# Ringlight.net
KiCad netlist of a schematic drawn in EAGLE
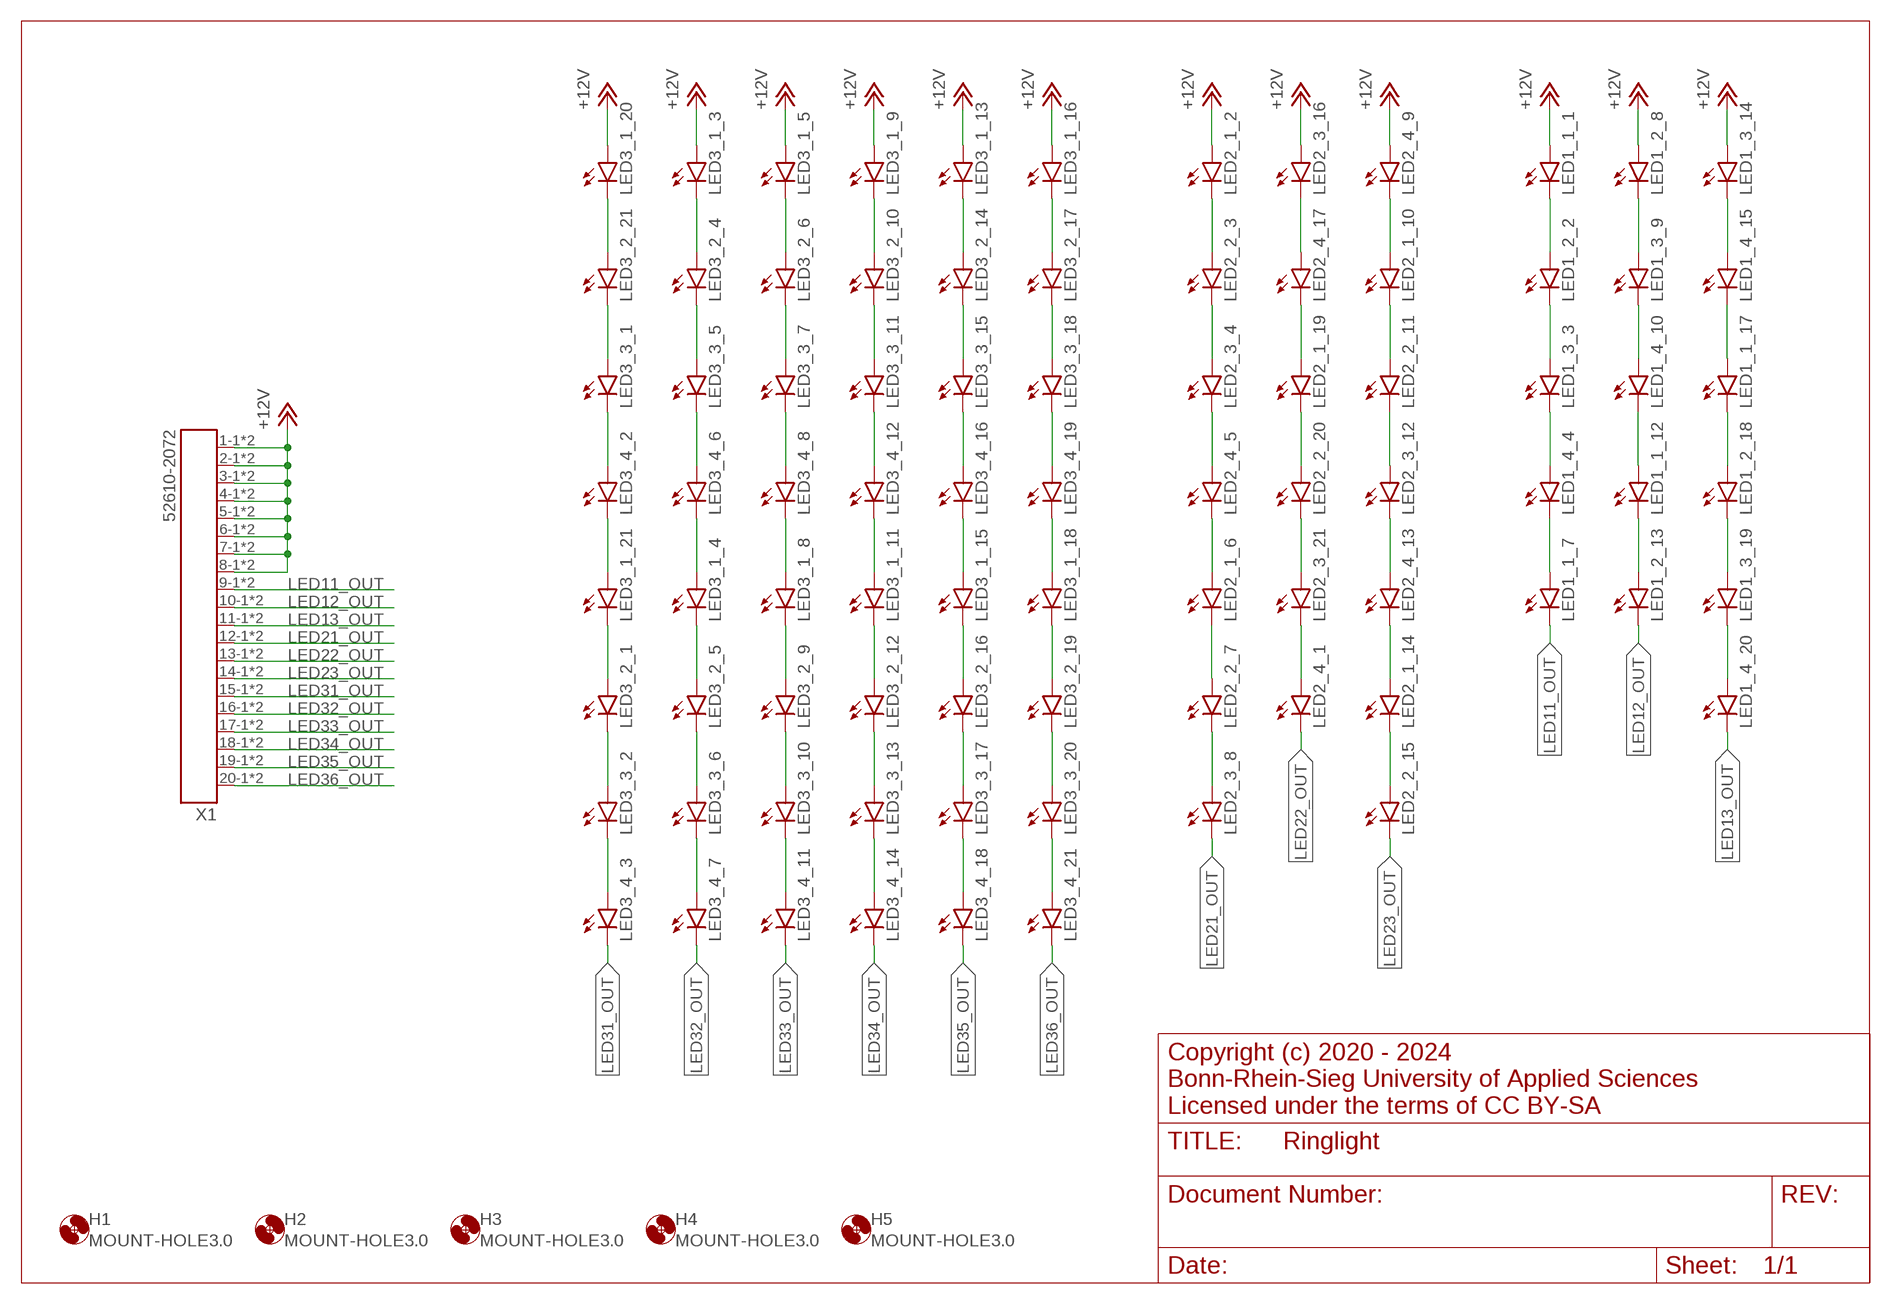
[diagram p0: schematic, sheet 1]

(export (version "E")
  (design (tool "Eeschema 10.0.6"))
  (components
    (comp (ref "H1")
      (value "MOUNT-HOLE3.0")
      (footprint "eagle-import:3,0")
      (libsource (lib "eagle-import") (part "MOUNT-HOLE3.0"))
    )
    (comp (ref "H2")
      (value "MOUNT-HOLE3.0")
      (footprint "eagle-import:3,0")
      (libsource (lib "eagle-import") (part "MOUNT-HOLE3.0"))
    )
    (comp (ref "H3")
      (value "MOUNT-HOLE3.0")
      (footprint "eagle-import:3,0")
      (libsource (lib "eagle-import") (part "MOUNT-HOLE3.0"))
    )
    (comp (ref "H4")
      (value "MOUNT-HOLE3.0")
      (footprint "eagle-import:3,0")
      (libsource (lib "eagle-import") (part "MOUNT-HOLE3.0"))
    )
    (comp (ref "H5")
      (value "MOUNT-HOLE3.0")
      (footprint "eagle-import:3,0")
      (libsource (lib "eagle-import") (part "MOUNT-HOLE3.0"))
    )
    (comp (ref "LED1_1_1")
      (value "LED5MM")
      (footprint "eagle-import:LED5MM")
      (libsource (lib "eagle-import") (part "LED5MM"))
    )
    (comp (ref "LED1_1_7")
      (value "LED5MM")
      (footprint "eagle-import:LED5MM")
      (libsource (lib "eagle-import") (part "LED5MM"))
    )
    (comp (ref "LED1_1_12")
      (value "LED5MM")
      (footprint "eagle-import:LED5MM")
      (libsource (lib "eagle-import") (part "LED5MM"))
    )
    (comp (ref "LED1_1_17")
      (value "LED5MM")
      (footprint "eagle-import:LED5MM")
      (libsource (lib "eagle-import") (part "LED5MM"))
    )
    (comp (ref "LED1_2_2")
      (value "LED5MM")
      (footprint "eagle-import:LED5MM")
      (libsource (lib "eagle-import") (part "LED5MM"))
    )
    (comp (ref "LED1_2_8")
      (value "LED5MM")
      (footprint "eagle-import:LED5MM")
      (libsource (lib "eagle-import") (part "LED5MM"))
    )
    (comp (ref "LED1_2_13")
      (value "LED5MM")
      (footprint "eagle-import:LED5MM")
      (libsource (lib "eagle-import") (part "LED5MM"))
    )
    (comp (ref "LED1_2_18")
      (value "LED5MM")
      (footprint "eagle-import:LED5MM")
      (libsource (lib "eagle-import") (part "LED5MM"))
    )
    (comp (ref "LED1_3_3")
      (value "LED5MM")
      (footprint "eagle-import:LED5MM")
      (libsource (lib "eagle-import") (part "LED5MM"))
    )
    (comp (ref "LED1_3_9")
      (value "LED5MM")
      (footprint "eagle-import:LED5MM")
      (libsource (lib "eagle-import") (part "LED5MM"))
    )
    (comp (ref "LED1_3_14")
      (value "LED5MM")
      (footprint "eagle-import:LED5MM")
      (libsource (lib "eagle-import") (part "LED5MM"))
    )
    (comp (ref "LED1_3_19")
      (value "LED5MM")
      (footprint "eagle-import:LED5MM")
      (libsource (lib "eagle-import") (part "LED5MM"))
    )
    (comp (ref "LED1_4_4")
      (value "LED5MM")
      (footprint "eagle-import:LED5MM")
      (libsource (lib "eagle-import") (part "LED5MM"))
    )
    (comp (ref "LED1_4_10")
      (value "LED5MM")
      (footprint "eagle-import:LED5MM")
      (libsource (lib "eagle-import") (part "LED5MM"))
    )
    (comp (ref "LED1_4_15")
      (value "LED5MM")
      (footprint "eagle-import:LED5MM")
      (libsource (lib "eagle-import") (part "LED5MM"))
    )
    (comp (ref "LED1_4_20")
      (value "LED5MM")
      (footprint "eagle-import:LED5MM")
      (libsource (lib "eagle-import") (part "LED5MM"))
    )
    (comp (ref "LED2_1_2")
      (value "LED5MM")
      (footprint "eagle-import:LED5MM")
      (libsource (lib "eagle-import") (part "LED5MM"))
    )
    (comp (ref "LED2_1_6")
      (value "LED5MM")
      (footprint "eagle-import:LED5MM")
      (libsource (lib "eagle-import") (part "LED5MM"))
    )
    (comp (ref "LED2_1_10")
      (value "LED5MM")
      (footprint "eagle-import:LED5MM")
      (libsource (lib "eagle-import") (part "LED5MM"))
    )
    (comp (ref "LED2_1_14")
      (value "LED5MM")
      (footprint "eagle-import:LED5MM")
      (libsource (lib "eagle-import") (part "LED5MM"))
    )
    (comp (ref "LED2_1_19")
      (value "LED5MM")
      (footprint "eagle-import:LED5MM")
      (libsource (lib "eagle-import") (part "LED5MM"))
    )
    (comp (ref "LED2_2_3")
      (value "LED5MM")
      (footprint "eagle-import:LED5MM")
      (libsource (lib "eagle-import") (part "LED5MM"))
    )
    (comp (ref "LED2_2_7")
      (value "LED5MM")
      (footprint "eagle-import:LED5MM")
      (libsource (lib "eagle-import") (part "LED5MM"))
    )
    (comp (ref "LED2_2_11")
      (value "LED5MM")
      (footprint "eagle-import:LED5MM")
      (libsource (lib "eagle-import") (part "LED5MM"))
    )
    (comp (ref "LED2_2_15")
      (value "LED5MM")
      (footprint "eagle-import:LED5MM")
      (libsource (lib "eagle-import") (part "LED5MM"))
    )
    (comp (ref "LED2_2_20")
      (value "LED5MM")
      (footprint "eagle-import:LED5MM")
      (libsource (lib "eagle-import") (part "LED5MM"))
    )
    (comp (ref "LED2_3_4")
      (value "LED5MM")
      (footprint "eagle-import:LED5MM")
      (libsource (lib "eagle-import") (part "LED5MM"))
    )
    (comp (ref "LED2_3_8")
      (value "LED5MM")
      (footprint "eagle-import:LED5MM")
      (libsource (lib "eagle-import") (part "LED5MM"))
    )
    (comp (ref "LED2_3_12")
      (value "LED5MM")
      (footprint "eagle-import:LED5MM")
      (libsource (lib "eagle-import") (part "LED5MM"))
    )
    (comp (ref "LED2_3_16")
      (value "LED5MM")
      (footprint "eagle-import:LED5MM")
      (libsource (lib "eagle-import") (part "LED5MM"))
    )
    (comp (ref "LED2_3_21")
      (value "LED5MM")
      (footprint "eagle-import:LED5MM")
      (libsource (lib "eagle-import") (part "LED5MM"))
    )
    (comp (ref "LED2_4_1")
      (value "LED5MM")
      (footprint "eagle-import:LED5MM")
      (libsource (lib "eagle-import") (part "LED5MM"))
    )
    (comp (ref "LED2_4_5")
      (value "LED5MM")
      (footprint "eagle-import:LED5MM")
      (libsource (lib "eagle-import") (part "LED5MM"))
    )
    (comp (ref "LED2_4_9")
      (value "LED5MM")
      (footprint "eagle-import:LED5MM")
      (libsource (lib "eagle-import") (part "LED5MM"))
    )
    (comp (ref "LED2_4_13")
      (value "LED5MM")
      (footprint "eagle-import:LED5MM")
      (libsource (lib "eagle-import") (part "LED5MM"))
    )
    (comp (ref "LED2_4_17")
      (value "LED5MM")
      (footprint "eagle-import:LED5MM")
      (libsource (lib "eagle-import") (part "LED5MM"))
    )
    (comp (ref "LED3_1_3")
      (value "LED5MM")
      (footprint "eagle-import:LED5MM")
      (libsource (lib "eagle-import") (part "LED5MM"))
    )
    (comp (ref "LED3_1_4")
      (value "LED5MM")
      (footprint "eagle-import:LED5MM")
      (libsource (lib "eagle-import") (part "LED5MM"))
    )
    (comp (ref "LED3_1_5")
      (value "LED5MM")
      (footprint "eagle-import:LED5MM")
      (libsource (lib "eagle-import") (part "LED5MM"))
    )
    (comp (ref "LED3_1_8")
      (value "LED5MM")
      (footprint "eagle-import:LED5MM")
      (libsource (lib "eagle-import") (part "LED5MM"))
    )
    (comp (ref "LED3_1_9")
      (value "LED5MM")
      (footprint "eagle-import:LED5MM")
      (libsource (lib "eagle-import") (part "LED5MM"))
    )
    (comp (ref "LED3_1_11")
      (value "LED5MM")
      (footprint "eagle-import:LED5MM")
      (libsource (lib "eagle-import") (part "LED5MM"))
    )
    (comp (ref "LED3_1_13")
      (value "LED5MM")
      (footprint "eagle-import:LED5MM")
      (libsource (lib "eagle-import") (part "LED5MM"))
    )
    (comp (ref "LED3_1_15")
      (value "LED5MM")
      (footprint "eagle-import:LED5MM")
      (libsource (lib "eagle-import") (part "LED5MM"))
    )
    (comp (ref "LED3_1_16")
      (value "LED5MM")
      (footprint "eagle-import:LED5MM")
      (libsource (lib "eagle-import") (part "LED5MM"))
    )
    (comp (ref "LED3_1_18")
      (value "LED5MM")
      (footprint "eagle-import:LED5MM")
      (libsource (lib "eagle-import") (part "LED5MM"))
    )
    (comp (ref "LED3_1_20")
      (value "LED5MM")
      (footprint "eagle-import:LED5MM")
      (libsource (lib "eagle-import") (part "LED5MM"))
    )
    (comp (ref "LED3_1_21")
      (value "LED5MM")
      (footprint "eagle-import:LED5MM")
      (libsource (lib "eagle-import") (part "LED5MM"))
    )
    (comp (ref "LED3_2_1")
      (value "LED5MM")
      (footprint "eagle-import:LED5MM")
      (libsource (lib "eagle-import") (part "LED5MM"))
    )
    (comp (ref "LED3_2_4")
      (value "LED5MM")
      (footprint "eagle-import:LED5MM")
      (libsource (lib "eagle-import") (part "LED5MM"))
    )
    (comp (ref "LED3_2_5")
      (value "LED5MM")
      (footprint "eagle-import:LED5MM")
      (libsource (lib "eagle-import") (part "LED5MM"))
    )
    (comp (ref "LED3_2_6")
      (value "LED5MM")
      (footprint "eagle-import:LED5MM")
      (libsource (lib "eagle-import") (part "LED5MM"))
    )
    (comp (ref "LED3_2_9")
      (value "LED5MM")
      (footprint "eagle-import:LED5MM")
      (libsource (lib "eagle-import") (part "LED5MM"))
    )
    (comp (ref "LED3_2_10")
      (value "LED5MM")
      (footprint "eagle-import:LED5MM")
      (libsource (lib "eagle-import") (part "LED5MM"))
    )
    (comp (ref "LED3_2_12")
      (value "LED5MM")
      (footprint "eagle-import:LED5MM")
      (libsource (lib "eagle-import") (part "LED5MM"))
    )
    (comp (ref "LED3_2_14")
      (value "LED5MM")
      (footprint "eagle-import:LED5MM")
      (libsource (lib "eagle-import") (part "LED5MM"))
    )
    (comp (ref "LED3_2_16")
      (value "LED5MM")
      (footprint "eagle-import:LED5MM")
      (libsource (lib "eagle-import") (part "LED5MM"))
    )
    (comp (ref "LED3_2_17")
      (value "LED5MM")
      (footprint "eagle-import:LED5MM")
      (libsource (lib "eagle-import") (part "LED5MM"))
    )
    (comp (ref "LED3_2_19")
      (value "LED5MM")
      (footprint "eagle-import:LED5MM")
      (libsource (lib "eagle-import") (part "LED5MM"))
    )
    (comp (ref "LED3_2_21")
      (value "LED5MM")
      (footprint "eagle-import:LED5MM")
      (libsource (lib "eagle-import") (part "LED5MM"))
    )
    (comp (ref "LED3_3_1")
      (value "LED5MM")
      (footprint "eagle-import:LED5MM")
      (libsource (lib "eagle-import") (part "LED5MM"))
    )
    (comp (ref "LED3_3_2")
      (value "LED5MM")
      (footprint "eagle-import:LED5MM")
      (libsource (lib "eagle-import") (part "LED5MM"))
    )
    (comp (ref "LED3_3_5")
      (value "LED5MM")
      (footprint "eagle-import:LED5MM")
      (libsource (lib "eagle-import") (part "LED5MM"))
    )
    (comp (ref "LED3_3_6")
      (value "LED5MM")
      (footprint "eagle-import:LED5MM")
      (libsource (lib "eagle-import") (part "LED5MM"))
    )
    (comp (ref "LED3_3_7")
      (value "LED5MM")
      (footprint "eagle-import:LED5MM")
      (libsource (lib "eagle-import") (part "LED5MM"))
    )
    (comp (ref "LED3_3_10")
      (value "LED5MM")
      (footprint "eagle-import:LED5MM")
      (libsource (lib "eagle-import") (part "LED5MM"))
    )
    (comp (ref "LED3_3_11")
      (value "LED5MM")
      (footprint "eagle-import:LED5MM")
      (libsource (lib "eagle-import") (part "LED5MM"))
    )
    (comp (ref "LED3_3_13")
      (value "LED5MM")
      (footprint "eagle-import:LED5MM")
      (libsource (lib "eagle-import") (part "LED5MM"))
    )
    (comp (ref "LED3_3_15")
      (value "LED5MM")
      (footprint "eagle-import:LED5MM")
      (libsource (lib "eagle-import") (part "LED5MM"))
    )
    (comp (ref "LED3_3_17")
      (value "LED5MM")
      (footprint "eagle-import:LED5MM")
      (libsource (lib "eagle-import") (part "LED5MM"))
    )
    (comp (ref "LED3_3_18")
      (value "LED5MM")
      (footprint "eagle-import:LED5MM")
      (libsource (lib "eagle-import") (part "LED5MM"))
    )
    (comp (ref "LED3_3_20")
      (value "LED5MM")
      (footprint "eagle-import:LED5MM")
      (libsource (lib "eagle-import") (part "LED5MM"))
    )
    (comp (ref "LED3_4_2")
      (value "LED5MM")
      (footprint "eagle-import:LED5MM")
      (libsource (lib "eagle-import") (part "LED5MM"))
    )
    (comp (ref "LED3_4_3")
      (value "LED5MM")
      (footprint "eagle-import:LED5MM")
      (libsource (lib "eagle-import") (part "LED5MM"))
    )
    (comp (ref "LED3_4_6")
      (value "LED5MM")
      (footprint "eagle-import:LED5MM")
      (libsource (lib "eagle-import") (part "LED5MM"))
    )
    (comp (ref "LED3_4_7")
      (value "LED5MM")
      (footprint "eagle-import:LED5MM")
      (libsource (lib "eagle-import") (part "LED5MM"))
    )
    (comp (ref "LED3_4_8")
      (value "LED5MM")
      (footprint "eagle-import:LED5MM")
      (libsource (lib "eagle-import") (part "LED5MM"))
    )
    (comp (ref "LED3_4_11")
      (value "LED5MM")
      (footprint "eagle-import:LED5MM")
      (libsource (lib "eagle-import") (part "LED5MM"))
    )
    (comp (ref "LED3_4_12")
      (value "LED5MM")
      (footprint "eagle-import:LED5MM")
      (libsource (lib "eagle-import") (part "LED5MM"))
    )
    (comp (ref "LED3_4_14")
      (value "LED5MM")
      (footprint "eagle-import:LED5MM")
      (libsource (lib "eagle-import") (part "LED5MM"))
    )
    (comp (ref "LED3_4_16")
      (value "LED5MM")
      (footprint "eagle-import:LED5MM")
      (libsource (lib "eagle-import") (part "LED5MM"))
    )
    (comp (ref "LED3_4_18")
      (value "LED5MM")
      (footprint "eagle-import:LED5MM")
      (libsource (lib "eagle-import") (part "LED5MM"))
    )
    (comp (ref "LED3_4_19")
      (value "LED5MM")
      (footprint "eagle-import:LED5MM")
      (libsource (lib "eagle-import") (part "LED5MM"))
    )
    (comp (ref "LED3_4_21")
      (value "LED5MM")
      (footprint "eagle-import:LED5MM")
      (libsource (lib "eagle-import") (part "LED5MM"))
    )
    (comp (ref "X1")
      (value "52610-2072")
      (footprint "eagle-import:52610-2072")
      (libsource (lib "eagle-import") (part "52610-2072"))
    )
  )
  (nets
    (net (code "1") (name "+12V") (class "Default")
      (node (ref "LED1_1_1") (pin "A") (pinfunction "A_A") (pintype "passive"))
      (node (ref "LED1_2_8") (pin "A") (pinfunction "A_A") (pintype "passive"))
      (node (ref "LED1_3_14") (pin "A") (pinfunction "A_A") (pintype "passive"))
      (node (ref "LED2_1_2") (pin "A") (pinfunction "A_A") (pintype "passive"))
      (node (ref "LED2_3_16") (pin "A") (pinfunction "A_A") (pintype "passive"))
      (node (ref "LED2_4_9") (pin "A") (pinfunction "A_A") (pintype "passive"))
      (node (ref "LED3_1_13") (pin "A") (pinfunction "A_A") (pintype "passive"))
      (node (ref "LED3_1_16") (pin "A") (pinfunction "A_A") (pintype "passive"))
      (node (ref "LED3_1_20") (pin "A") (pinfunction "A_A") (pintype "passive"))
      (node (ref "LED3_1_3") (pin "A") (pinfunction "A_A") (pintype "passive"))
      (node (ref "LED3_1_5") (pin "A") (pinfunction "A_A") (pintype "passive"))
      (node (ref "LED3_1_9") (pin "A") (pinfunction "A_A") (pintype "passive"))
      (node (ref "X1") (pin "1-1") (pinfunction "1_1-1") (pintype "bidirectional"))
      (node (ref "X1") (pin "1-2") (pinfunction "1_1-2") (pintype "bidirectional"))
      (node (ref "X1") (pin "2-1") (pinfunction "2_2-1") (pintype "bidirectional"))
      (node (ref "X1") (pin "2-2") (pinfunction "2_2-2") (pintype "bidirectional"))
      (node (ref "X1") (pin "3-1") (pinfunction "3_3-1") (pintype "bidirectional"))
      (node (ref "X1") (pin "3-2") (pinfunction "3_3-2") (pintype "bidirectional"))
      (node (ref "X1") (pin "4-1") (pinfunction "4_4-1") (pintype "bidirectional"))
      (node (ref "X1") (pin "4-2") (pinfunction "4_4-2") (pintype "bidirectional"))
      (node (ref "X1") (pin "5-1") (pinfunction "5_5-1") (pintype "bidirectional"))
      (node (ref "X1") (pin "5-2") (pinfunction "5_5-2") (pintype "bidirectional"))
      (node (ref "X1") (pin "6-1") (pinfunction "6_6-1") (pintype "bidirectional"))
      (node (ref "X1") (pin "6-2") (pinfunction "6_6-2") (pintype "bidirectional"))
      (node (ref "X1") (pin "7-1") (pinfunction "7_7-1") (pintype "bidirectional"))
      (node (ref "X1") (pin "7-2") (pinfunction "7_7-2") (pintype "bidirectional"))
      (node (ref "X1") (pin "8-1") (pinfunction "8_8-1") (pintype "bidirectional"))
      (node (ref "X1") (pin "8-2") (pinfunction "8_8-2") (pintype "bidirectional"))
    )
    (net (code "2") (name "LED11_OUT") (class "Default")
      (node (ref "LED1_1_7") (pin "K") (pinfunction "C_K") (pintype "passive"))
      (node (ref "X1") (pin "9-1") (pinfunction "9_9-1") (pintype "bidirectional"))
      (node (ref "X1") (pin "9-2") (pinfunction "9_9-2") (pintype "bidirectional"))
    )
    (net (code "3") (name "LED12_OUT") (class "Default")
      (node (ref "LED1_2_13") (pin "K") (pinfunction "C_K") (pintype "passive"))
      (node (ref "X1") (pin "10-1") (pinfunction "10_10-1") (pintype "bidirectional"))
      (node (ref "X1") (pin "10-2") (pinfunction "10_10-2") (pintype "bidirectional"))
    )
    (net (code "4") (name "LED13_OUT") (class "Default")
      (node (ref "LED1_4_20") (pin "K") (pinfunction "C_K") (pintype "passive"))
      (node (ref "X1") (pin "11-1") (pinfunction "11_11-1") (pintype "bidirectional"))
      (node (ref "X1") (pin "11-2") (pinfunction "11_11-2") (pintype "bidirectional"))
    )
    (net (code "5") (name "LED21_OUT") (class "Default")
      (node (ref "LED2_3_8") (pin "K") (pinfunction "C_K") (pintype "passive"))
      (node (ref "X1") (pin "12-1") (pinfunction "12_12-1") (pintype "bidirectional"))
      (node (ref "X1") (pin "12-2") (pinfunction "12_12-2") (pintype "bidirectional"))
    )
    (net (code "6") (name "LED22_OUT") (class "Default")
      (node (ref "LED2_4_1") (pin "K") (pinfunction "C_K") (pintype "passive"))
      (node (ref "X1") (pin "13-1") (pinfunction "13_13-1") (pintype "bidirectional"))
      (node (ref "X1") (pin "13-2") (pinfunction "13_13-2") (pintype "bidirectional"))
    )
    (net (code "7") (name "LED23_OUT") (class "Default")
      (node (ref "LED2_2_15") (pin "K") (pinfunction "C_K") (pintype "passive"))
      (node (ref "X1") (pin "14-1") (pinfunction "14_14-1") (pintype "bidirectional"))
      (node (ref "X1") (pin "14-2") (pinfunction "14_14-2") (pintype "bidirectional"))
    )
    (net (code "8") (name "LED31_OUT") (class "Default")
      (node (ref "LED3_4_3") (pin "K") (pinfunction "C_K") (pintype "passive"))
      (node (ref "X1") (pin "15-1") (pinfunction "15_15-1") (pintype "bidirectional"))
      (node (ref "X1") (pin "15-2") (pinfunction "15_15-2") (pintype "bidirectional"))
    )
    (net (code "9") (name "LED32_OUT") (class "Default")
      (node (ref "LED3_4_7") (pin "K") (pinfunction "C_K") (pintype "passive"))
      (node (ref "X1") (pin "16-1") (pinfunction "16_16-1") (pintype "bidirectional"))
      (node (ref "X1") (pin "16-2") (pinfunction "16_16-2") (pintype "bidirectional"))
    )
    (net (code "10") (name "LED33_OUT") (class "Default")
      (node (ref "LED3_4_11") (pin "K") (pinfunction "C_K") (pintype "passive"))
      (node (ref "X1") (pin "17-1") (pinfunction "17_17-1") (pintype "bidirectional"))
      (node (ref "X1") (pin "17-2") (pinfunction "17_17-2") (pintype "bidirectional"))
    )
    (net (code "11") (name "LED34_OUT") (class "Default")
      (node (ref "LED3_4_14") (pin "K") (pinfunction "C_K") (pintype "passive"))
      (node (ref "X1") (pin "18-1") (pinfunction "18_18-1") (pintype "bidirectional"))
      (node (ref "X1") (pin "18-2") (pinfunction "18_18-2") (pintype "bidirectional"))
    )
    (net (code "12") (name "LED35_OUT") (class "Default")
      (node (ref "LED3_4_18") (pin "K") (pinfunction "C_K") (pintype "passive"))
      (node (ref "X1") (pin "19-1") (pinfunction "19_19-1") (pintype "bidirectional"))
      (node (ref "X1") (pin "19-2") (pinfunction "19_19-2") (pintype "bidirectional"))
    )
    (net (code "13") (name "LED36_OUT") (class "Default")
      (node (ref "LED3_4_21") (pin "K") (pinfunction "C_K") (pintype "passive"))
      (node (ref "X1") (pin "20-1") (pinfunction "20_20-1") (pintype "bidirectional"))
      (node (ref "X1") (pin "20-2") (pinfunction "20_20-2") (pintype "bidirectional"))
    )
    (net (code "14") (name "Net-(LED1_1_1-C)") (class "Default")
      (node (ref "LED1_1_1") (pin "K") (pinfunction "C_K") (pintype "passive"))
      (node (ref "LED1_2_2") (pin "A") (pinfunction "A_A") (pintype "passive"))
    )
    (net (code "15") (name "Net-(LED1_1_12-C)") (class "Default")
      (node (ref "LED1_1_12") (pin "K") (pinfunction "C_K") (pintype "passive"))
      (node (ref "LED1_2_13") (pin "A") (pinfunction "A_A") (pintype "passive"))
    )
    (net (code "16") (name "Net-(LED1_1_17-C)") (class "Default")
      (node (ref "LED1_1_17") (pin "K") (pinfunction "C_K") (pintype "passive"))
      (node (ref "LED1_2_18") (pin "A") (pinfunction "A_A") (pintype "passive"))
    )
    (net (code "17") (name "Net-(LED1_2_2-C)") (class "Default")
      (node (ref "LED1_2_2") (pin "K") (pinfunction "C_K") (pintype "passive"))
      (node (ref "LED1_3_3") (pin "A") (pinfunction "A_A") (pintype "passive"))
    )
    (net (code "18") (name "Net-(LED1_2_8-C)") (class "Default")
      (node (ref "LED1_2_8") (pin "K") (pinfunction "C_K") (pintype "passive"))
      (node (ref "LED1_3_9") (pin "A") (pinfunction "A_A") (pintype "passive"))
    )
    (net (code "19") (name "Net-(LED1_2_18-C)") (class "Default")
      (node (ref "LED1_2_18") (pin "K") (pinfunction "C_K") (pintype "passive"))
      (node (ref "LED1_3_19") (pin "A") (pinfunction "A_A") (pintype "passive"))
    )
    (net (code "20") (name "Net-(LED1_3_3-C)") (class "Default")
      (node (ref "LED1_3_3") (pin "K") (pinfunction "C_K") (pintype "passive"))
      (node (ref "LED1_4_4") (pin "A") (pinfunction "A_A") (pintype "passive"))
    )
    (net (code "21") (name "Net-(LED1_3_9-C)") (class "Default")
      (node (ref "LED1_3_9") (pin "K") (pinfunction "C_K") (pintype "passive"))
      (node (ref "LED1_4_10") (pin "A") (pinfunction "A_A") (pintype "passive"))
    )
    (net (code "22") (name "Net-(LED1_3_14-C)") (class "Default")
      (node (ref "LED1_3_14") (pin "K") (pinfunction "C_K") (pintype "passive"))
      (node (ref "LED1_4_15") (pin "A") (pinfunction "A_A") (pintype "passive"))
    )
    (net (code "23") (name "Net-(LED1_3_19-C)") (class "Default")
      (node (ref "LED1_3_19") (pin "K") (pinfunction "C_K") (pintype "passive"))
      (node (ref "LED1_4_20") (pin "A") (pinfunction "A_A") (pintype "passive"))
    )
    (net (code "24") (name "Net-(LED1_4_4-C)") (class "Default")
      (node (ref "LED1_1_7") (pin "A") (pinfunction "A_A") (pintype "passive"))
      (node (ref "LED1_4_4") (pin "K") (pinfunction "C_K") (pintype "passive"))
    )
    (net (code "25") (name "Net-(LED1_4_10-C)") (class "Default")
      (node (ref "LED1_1_12") (pin "A") (pinfunction "A_A") (pintype "passive"))
      (node (ref "LED1_4_10") (pin "K") (pinfunction "C_K") (pintype "passive"))
    )
    (net (code "26") (name "Net-(LED1_4_15-C)") (class "Default")
      (node (ref "LED1_1_17") (pin "A") (pinfunction "A_A") (pintype "passive"))
      (node (ref "LED1_4_15") (pin "K") (pinfunction "C_K") (pintype "passive"))
    )
    (net (code "27") (name "Net-(LED2_1_2-C)") (class "Default")
      (node (ref "LED2_1_2") (pin "K") (pinfunction "C_K") (pintype "passive"))
      (node (ref "LED2_2_3") (pin "A") (pinfunction "A_A") (pintype "passive"))
    )
    (net (code "28") (name "Net-(LED2_1_6-C)") (class "Default")
      (node (ref "LED2_1_6") (pin "K") (pinfunction "C_K") (pintype "passive"))
      (node (ref "LED2_2_7") (pin "A") (pinfunction "A_A") (pintype "passive"))
    )
    (net (code "29") (name "Net-(LED2_1_10-C)") (class "Default")
      (node (ref "LED2_1_10") (pin "K") (pinfunction "C_K") (pintype "passive"))
      (node (ref "LED2_2_11") (pin "A") (pinfunction "A_A") (pintype "passive"))
    )
    (net (code "30") (name "Net-(LED2_1_14-C)") (class "Default")
      (node (ref "LED2_1_14") (pin "K") (pinfunction "C_K") (pintype "passive"))
      (node (ref "LED2_2_15") (pin "A") (pinfunction "A_A") (pintype "passive"))
    )
    (net (code "31") (name "Net-(LED2_1_19-C)") (class "Default")
      (node (ref "LED2_1_19") (pin "K") (pinfunction "C_K") (pintype "passive"))
      (node (ref "LED2_2_20") (pin "A") (pinfunction "A_A") (pintype "passive"))
    )
    (net (code "32") (name "Net-(LED2_2_3-C)") (class "Default")
      (node (ref "LED2_2_3") (pin "K") (pinfunction "C_K") (pintype "passive"))
      (node (ref "LED2_3_4") (pin "A") (pinfunction "A_A") (pintype "passive"))
    )
    (net (code "33") (name "Net-(LED2_2_7-C)") (class "Default")
      (node (ref "LED2_2_7") (pin "K") (pinfunction "C_K") (pintype "passive"))
      (node (ref "LED2_3_8") (pin "A") (pinfunction "A_A") (pintype "passive"))
    )
    (net (code "34") (name "Net-(LED2_2_11-C)") (class "Default")
      (node (ref "LED2_2_11") (pin "K") (pinfunction "C_K") (pintype "passive"))
      (node (ref "LED2_3_12") (pin "A") (pinfunction "A_A") (pintype "passive"))
    )
    (net (code "35") (name "Net-(LED2_2_20-C)") (class "Default")
      (node (ref "LED2_2_20") (pin "K") (pinfunction "C_K") (pintype "passive"))
      (node (ref "LED2_3_21") (pin "A") (pinfunction "A_A") (pintype "passive"))
    )
    (net (code "36") (name "Net-(LED2_3_4-C)") (class "Default")
      (node (ref "LED2_3_4") (pin "K") (pinfunction "C_K") (pintype "passive"))
      (node (ref "LED2_4_5") (pin "A") (pinfunction "A_A") (pintype "passive"))
    )
    (net (code "37") (name "Net-(LED2_3_12-C)") (class "Default")
      (node (ref "LED2_3_12") (pin "K") (pinfunction "C_K") (pintype "passive"))
      (node (ref "LED2_4_13") (pin "A") (pinfunction "A_A") (pintype "passive"))
    )
    (net (code "38") (name "Net-(LED2_3_16-C)") (class "Default")
      (node (ref "LED2_3_16") (pin "K") (pinfunction "C_K") (pintype "passive"))
      (node (ref "LED2_4_17") (pin "A") (pinfunction "A_A") (pintype "passive"))
    )
    (net (code "39") (name "Net-(LED2_3_21-C)") (class "Default")
      (node (ref "LED2_3_21") (pin "K") (pinfunction "C_K") (pintype "passive"))
      (node (ref "LED2_4_1") (pin "A") (pinfunction "A_A") (pintype "passive"))
    )
    (net (code "40") (name "Net-(LED2_4_5-C)") (class "Default")
      (node (ref "LED2_1_6") (pin "A") (pinfunction "A_A") (pintype "passive"))
      (node (ref "LED2_4_5") (pin "K") (pinfunction "C_K") (pintype "passive"))
    )
    (net (code "41") (name "Net-(LED2_4_9-C)") (class "Default")
      (node (ref "LED2_1_10") (pin "A") (pinfunction "A_A") (pintype "passive"))
      (node (ref "LED2_4_9") (pin "K") (pinfunction "C_K") (pintype "passive"))
    )
    (net (code "42") (name "Net-(LED2_4_13-C)") (class "Default")
      (node (ref "LED2_1_14") (pin "A") (pinfunction "A_A") (pintype "passive"))
      (node (ref "LED2_4_13") (pin "K") (pinfunction "C_K") (pintype "passive"))
    )
    (net (code "43") (name "Net-(LED2_4_17-C)") (class "Default")
      (node (ref "LED2_1_19") (pin "A") (pinfunction "A_A") (pintype "passive"))
      (node (ref "LED2_4_17") (pin "K") (pinfunction "C_K") (pintype "passive"))
    )
    (net (code "44") (name "Net-(LED3_1_3-C)") (class "Default")
      (node (ref "LED3_1_3") (pin "K") (pinfunction "C_K") (pintype "passive"))
      (node (ref "LED3_2_4") (pin "A") (pinfunction "A_A") (pintype "passive"))
    )
    (net (code "45") (name "Net-(LED3_1_4-C)") (class "Default")
      (node (ref "LED3_1_4") (pin "K") (pinfunction "C_K") (pintype "passive"))
      (node (ref "LED3_2_5") (pin "A") (pinfunction "A_A") (pintype "passive"))
    )
    (net (code "46") (name "Net-(LED3_1_5-C)") (class "Default")
      (node (ref "LED3_1_5") (pin "K") (pinfunction "C_K") (pintype "passive"))
      (node (ref "LED3_2_6") (pin "A") (pinfunction "A_A") (pintype "passive"))
    )
    (net (code "47") (name "Net-(LED3_1_8-C)") (class "Default")
      (node (ref "LED3_1_8") (pin "K") (pinfunction "C_K") (pintype "passive"))
      (node (ref "LED3_2_9") (pin "A") (pinfunction "A_A") (pintype "passive"))
    )
    (net (code "48") (name "Net-(LED3_1_9-C)") (class "Default")
      (node (ref "LED3_1_9") (pin "K") (pinfunction "C_K") (pintype "passive"))
      (node (ref "LED3_2_10") (pin "A") (pinfunction "A_A") (pintype "passive"))
    )
    (net (code "49") (name "Net-(LED3_1_11-C)") (class "Default")
      (node (ref "LED3_1_11") (pin "K") (pinfunction "C_K") (pintype "passive"))
      (node (ref "LED3_2_12") (pin "A") (pinfunction "A_A") (pintype "passive"))
    )
    (net (code "50") (name "Net-(LED3_1_13-C)") (class "Default")
      (node (ref "LED3_1_13") (pin "K") (pinfunction "C_K") (pintype "passive"))
      (node (ref "LED3_2_14") (pin "A") (pinfunction "A_A") (pintype "passive"))
    )
    (net (code "51") (name "Net-(LED3_1_15-C)") (class "Default")
      (node (ref "LED3_1_15") (pin "K") (pinfunction "C_K") (pintype "passive"))
      (node (ref "LED3_2_16") (pin "A") (pinfunction "A_A") (pintype "passive"))
    )
    (net (code "52") (name "Net-(LED3_1_16-C)") (class "Default")
      (node (ref "LED3_1_16") (pin "K") (pinfunction "C_K") (pintype "passive"))
      (node (ref "LED3_2_17") (pin "A") (pinfunction "A_A") (pintype "passive"))
    )
    (net (code "53") (name "Net-(LED3_1_18-C)") (class "Default")
      (node (ref "LED3_1_18") (pin "K") (pinfunction "C_K") (pintype "passive"))
      (node (ref "LED3_2_19") (pin "A") (pinfunction "A_A") (pintype "passive"))
    )
    (net (code "54") (name "Net-(LED3_1_20-C)") (class "Default")
      (node (ref "LED3_1_20") (pin "K") (pinfunction "C_K") (pintype "passive"))
      (node (ref "LED3_2_21") (pin "A") (pinfunction "A_A") (pintype "passive"))
    )
    (net (code "55") (name "Net-(LED3_1_21-C)") (class "Default")
      (node (ref "LED3_1_21") (pin "K") (pinfunction "C_K") (pintype "passive"))
      (node (ref "LED3_2_1") (pin "A") (pinfunction "A_A") (pintype "passive"))
    )
    (net (code "56") (name "Net-(LED3_2_1-C)") (class "Default")
      (node (ref "LED3_2_1") (pin "K") (pinfunction "C_K") (pintype "passive"))
      (node (ref "LED3_3_2") (pin "A") (pinfunction "A_A") (pintype "passive"))
    )
    (net (code "57") (name "Net-(LED3_2_4-C)") (class "Default")
      (node (ref "LED3_2_4") (pin "K") (pinfunction "C_K") (pintype "passive"))
      (node (ref "LED3_3_5") (pin "A") (pinfunction "A_A") (pintype "passive"))
    )
    (net (code "58") (name "Net-(LED3_2_5-C)") (class "Default")
      (node (ref "LED3_2_5") (pin "K") (pinfunction "C_K") (pintype "passive"))
      (node (ref "LED3_3_6") (pin "A") (pinfunction "A_A") (pintype "passive"))
    )
    (net (code "59") (name "Net-(LED3_2_6-C)") (class "Default")
      (node (ref "LED3_2_6") (pin "K") (pinfunction "C_K") (pintype "passive"))
      (node (ref "LED3_3_7") (pin "A") (pinfunction "A_A") (pintype "passive"))
    )
    (net (code "60") (name "Net-(LED3_2_9-C)") (class "Default")
      (node (ref "LED3_2_9") (pin "K") (pinfunction "C_K") (pintype "passive"))
      (node (ref "LED3_3_10") (pin "A") (pinfunction "A_A") (pintype "passive"))
    )
    (net (code "61") (name "Net-(LED3_2_10-C)") (class "Default")
      (node (ref "LED3_2_10") (pin "K") (pinfunction "C_K") (pintype "passive"))
      (node (ref "LED3_3_11") (pin "A") (pinfunction "A_A") (pintype "passive"))
    )
    (net (code "62") (name "Net-(LED3_2_12-C)") (class "Default")
      (node (ref "LED3_2_12") (pin "K") (pinfunction "C_K") (pintype "passive"))
      (node (ref "LED3_3_13") (pin "A") (pinfunction "A_A") (pintype "passive"))
    )
    (net (code "63") (name "Net-(LED3_2_14-C)") (class "Default")
      (node (ref "LED3_2_14") (pin "K") (pinfunction "C_K") (pintype "passive"))
      (node (ref "LED3_3_15") (pin "A") (pinfunction "A_A") (pintype "passive"))
    )
    (net (code "64") (name "Net-(LED3_2_16-C)") (class "Default")
      (node (ref "LED3_2_16") (pin "K") (pinfunction "C_K") (pintype "passive"))
      (node (ref "LED3_3_17") (pin "A") (pinfunction "A_A") (pintype "passive"))
    )
    (net (code "65") (name "Net-(LED3_2_17-C)") (class "Default")
      (node (ref "LED3_2_17") (pin "K") (pinfunction "C_K") (pintype "passive"))
      (node (ref "LED3_3_18") (pin "A") (pinfunction "A_A") (pintype "passive"))
    )
    (net (code "66") (name "Net-(LED3_2_19-C)") (class "Default")
      (node (ref "LED3_2_19") (pin "K") (pinfunction "C_K") (pintype "passive"))
      (node (ref "LED3_3_20") (pin "A") (pinfunction "A_A") (pintype "passive"))
    )
    (net (code "67") (name "Net-(LED3_2_21-C)") (class "Default")
      (node (ref "LED3_2_21") (pin "K") (pinfunction "C_K") (pintype "passive"))
      (node (ref "LED3_3_1") (pin "A") (pinfunction "A_A") (pintype "passive"))
    )
    (net (code "68") (name "Net-(LED3_3_1-C)") (class "Default")
      (node (ref "LED3_3_1") (pin "K") (pinfunction "C_K") (pintype "passive"))
      (node (ref "LED3_4_2") (pin "A") (pinfunction "A_A") (pintype "passive"))
    )
    (net (code "69") (name "Net-(LED3_3_2-C)") (class "Default")
      (node (ref "LED3_3_2") (pin "K") (pinfunction "C_K") (pintype "passive"))
      (node (ref "LED3_4_3") (pin "A") (pinfunction "A_A") (pintype "passive"))
    )
    (net (code "70") (name "Net-(LED3_3_5-C)") (class "Default")
      (node (ref "LED3_3_5") (pin "K") (pinfunction "C_K") (pintype "passive"))
      (node (ref "LED3_4_6") (pin "A") (pinfunction "A_A") (pintype "passive"))
    )
    (net (code "71") (name "Net-(LED3_3_6-C)") (class "Default")
      (node (ref "LED3_3_6") (pin "K") (pinfunction "C_K") (pintype "passive"))
      (node (ref "LED3_4_7") (pin "A") (pinfunction "A_A") (pintype "passive"))
    )
    (net (code "72") (name "Net-(LED3_3_7-C)") (class "Default")
      (node (ref "LED3_3_7") (pin "K") (pinfunction "C_K") (pintype "passive"))
      (node (ref "LED3_4_8") (pin "A") (pinfunction "A_A") (pintype "passive"))
    )
    (net (code "73") (name "Net-(LED3_3_10-C)") (class "Default")
      (node (ref "LED3_3_10") (pin "K") (pinfunction "C_K") (pintype "passive"))
      (node (ref "LED3_4_11") (pin "A") (pinfunction "A_A") (pintype "passive"))
    )
    (net (code "74") (name "Net-(LED3_3_11-C)") (class "Default")
      (node (ref "LED3_3_11") (pin "K") (pinfunction "C_K") (pintype "passive"))
      (node (ref "LED3_4_12") (pin "A") (pinfunction "A_A") (pintype "passive"))
    )
    (net (code "75") (name "Net-(LED3_3_13-C)") (class "Default")
      (node (ref "LED3_3_13") (pin "K") (pinfunction "C_K") (pintype "passive"))
      (node (ref "LED3_4_14") (pin "A") (pinfunction "A_A") (pintype "passive"))
    )
    (net (code "76") (name "Net-(LED3_3_15-C)") (class "Default")
      (node (ref "LED3_3_15") (pin "K") (pinfunction "C_K") (pintype "passive"))
      (node (ref "LED3_4_16") (pin "A") (pinfunction "A_A") (pintype "passive"))
    )
    (net (code "77") (name "Net-(LED3_3_17-C)") (class "Default")
      (node (ref "LED3_3_17") (pin "K") (pinfunction "C_K") (pintype "passive"))
      (node (ref "LED3_4_18") (pin "A") (pinfunction "A_A") (pintype "passive"))
    )
    (net (code "78") (name "Net-(LED3_3_18-C)") (class "Default")
      (node (ref "LED3_3_18") (pin "K") (pinfunction "C_K") (pintype "passive"))
      (node (ref "LED3_4_19") (pin "A") (pinfunction "A_A") (pintype "passive"))
    )
    (net (code "79") (name "Net-(LED3_3_20-C)") (class "Default")
      (node (ref "LED3_3_20") (pin "K") (pinfunction "C_K") (pintype "passive"))
      (node (ref "LED3_4_21") (pin "A") (pinfunction "A_A") (pintype "passive"))
    )
    (net (code "80") (name "Net-(LED3_4_2-C)") (class "Default")
      (node (ref "LED3_1_21") (pin "A") (pinfunction "A_A") (pintype "passive"))
      (node (ref "LED3_4_2") (pin "K") (pinfunction "C_K") (pintype "passive"))
    )
    (net (code "81") (name "Net-(LED3_4_6-C)") (class "Default")
      (node (ref "LED3_1_4") (pin "A") (pinfunction "A_A") (pintype "passive"))
      (node (ref "LED3_4_6") (pin "K") (pinfunction "C_K") (pintype "passive"))
    )
    (net (code "82") (name "Net-(LED3_4_8-C)") (class "Default")
      (node (ref "LED3_1_8") (pin "A") (pinfunction "A_A") (pintype "passive"))
      (node (ref "LED3_4_8") (pin "K") (pinfunction "C_K") (pintype "passive"))
    )
    (net (code "83") (name "Net-(LED3_4_12-C)") (class "Default")
      (node (ref "LED3_1_11") (pin "A") (pinfunction "A_A") (pintype "passive"))
      (node (ref "LED3_4_12") (pin "K") (pinfunction "C_K") (pintype "passive"))
    )
    (net (code "84") (name "Net-(LED3_4_16-C)") (class "Default")
      (node (ref "LED3_1_15") (pin "A") (pinfunction "A_A") (pintype "passive"))
      (node (ref "LED3_4_16") (pin "K") (pinfunction "C_K") (pintype "passive"))
    )
    (net (code "85") (name "Net-(LED3_4_19-C)") (class "Default")
      (node (ref "LED3_1_18") (pin "A") (pinfunction "A_A") (pintype "passive"))
      (node (ref "LED3_4_19") (pin "K") (pinfunction "C_K") (pintype "passive"))
    )
  )
)
